# SAO_Area3001_S_WS2812_00.net
KiCad netlist of a schematic drawn in Altium Designer
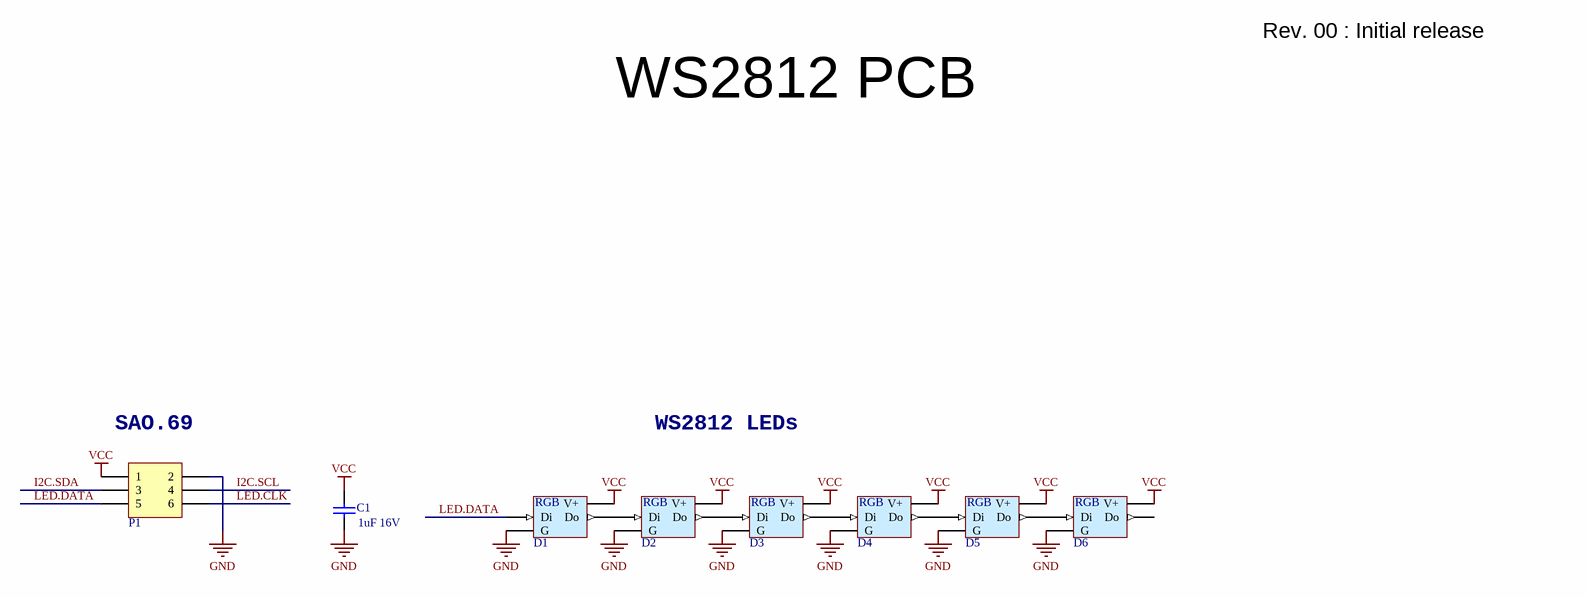
[diagram p0: SAO_Area3001_S_WS2812_00.SchDoc]

(export (version "E")
  (design (tool "Eeschema 10.0.6"))
  (components
    (comp (ref "C1")
      (value "1uF 16V")
      (footprint "C0603_N")
      (description "Capacitor Ceramic")
      (fields (field (name "Comment") "CAP_CERAMIC"))
      (libsource (lib "Phyx_Components") (part "CAP_CERAMIC"))
    )
    (comp (ref "D1")
      (value "WS2812 based digital RGB LED 2022 package")
      (footprint "LED_2022_WS2812B")
      (description "LED # RGB WS2812B-2022")
      (libsource (lib "Phyx_Components") (part "LED_RGB_WS2812B_2022"))
    )
    (comp (ref "D2")
      (value "WS2812 based digital RGB LED 2022 package")
      (footprint "LED_2022_WS2812B")
      (description "LED # RGB WS2812B-2022")
      (libsource (lib "Phyx_Components") (part "LED_RGB_WS2812B_2022"))
    )
    (comp (ref "D3")
      (value "WS2812 based digital RGB LED 2022 package")
      (footprint "LED_2022_WS2812B")
      (description "LED # RGB WS2812B-2022")
      (libsource (lib "Phyx_Components") (part "LED_RGB_WS2812B_2022"))
    )
    (comp (ref "D4")
      (value "WS2812 based digital RGB LED 2022 package")
      (footprint "LED_2022_WS2812B")
      (description "LED # RGB WS2812B-2022")
      (libsource (lib "Phyx_Components") (part "LED_RGB_WS2812B_2022"))
    )
    (comp (ref "D5")
      (value "WS2812 based digital RGB LED 2022 package")
      (footprint "LED_2022_WS2812B")
      (description "LED # RGB WS2812B-2022")
      (libsource (lib "Phyx_Components") (part "LED_RGB_WS2812B_2022"))
    )
    (comp (ref "D6")
      (value "WS2812 based digital RGB LED 2022 package")
      (footprint "LED_2022_WS2812B")
      (description "LED # RGB WS2812B-2022")
      (libsource (lib "Phyx_Components") (part "LED_RGB_WS2812B_2022"))
    )
    (comp (ref "P1")
      (value "Boxed Header 3X2")
      (footprint "HDR2X3_SMD")
      (libsource (lib "Phyx_Components") (part "Header 3X2"))
    )
  )
  (nets
    (net (code "1") (name "/I2C.SCL") (class "Default")
      (node (ref "P1") (pin "4") (pinfunction "4_4") (pintype "passive"))
    )
    (net (code "2") (name "/I2C.SDA") (class "Default")
      (node (ref "P1") (pin "3") (pinfunction "3_3") (pintype "passive"))
    )
    (net (code "3") (name "/LED.CLK") (class "Default")
      (node (ref "P1") (pin "6") (pinfunction "6_6") (pintype "passive"))
    )
    (net (code "4") (name "/LED.DATA") (class "Default")
      (node (ref "D1") (pin "3") (pinfunction "Di_3") (pintype "input"))
      (node (ref "P1") (pin "5") (pinfunction "5_5") (pintype "passive"))
    )
    (net (code "5") (name "GND") (class "Default")
      (node (ref "C1") (pin "2") (pinfunction "2_2") (pintype "passive"))
      (node (ref "D1") (pin "2") (pinfunction "G_2") (pintype "power_in"))
      (node (ref "D2") (pin "2") (pinfunction "G_2") (pintype "power_in"))
      (node (ref "D3") (pin "2") (pinfunction "G_2") (pintype "power_in"))
      (node (ref "D4") (pin "2") (pinfunction "G_2") (pintype "power_in"))
      (node (ref "D5") (pin "2") (pinfunction "G_2") (pintype "power_in"))
      (node (ref "D6") (pin "2") (pinfunction "G_2") (pintype "power_in"))
      (node (ref "P1") (pin "2") (pinfunction "2_2") (pintype "passive"))
    )
    (net (code "6") (name "Net-(D1-Do)") (class "Default")
      (node (ref "D1") (pin "1") (pinfunction "Do_1") (pintype "output"))
      (node (ref "D2") (pin "3") (pinfunction "Di_3") (pintype "input"))
    )
    (net (code "7") (name "Net-(D2-Do)") (class "Default")
      (node (ref "D2") (pin "1") (pinfunction "Do_1") (pintype "output"))
      (node (ref "D3") (pin "3") (pinfunction "Di_3") (pintype "input"))
    )
    (net (code "8") (name "Net-(D3-Do)") (class "Default")
      (node (ref "D3") (pin "1") (pinfunction "Do_1") (pintype "output"))
      (node (ref "D4") (pin "3") (pinfunction "Di_3") (pintype "input"))
    )
    (net (code "9") (name "Net-(D4-Do)") (class "Default")
      (node (ref "D4") (pin "1") (pinfunction "Do_1") (pintype "output"))
      (node (ref "D5") (pin "3") (pinfunction "Di_3") (pintype "input"))
    )
    (net (code "10") (name "Net-(D5-Do)") (class "Default")
      (node (ref "D5") (pin "1") (pinfunction "Do_1") (pintype "output"))
      (node (ref "D6") (pin "3") (pinfunction "Di_3") (pintype "input"))
    )
    (net (code "11") (name "VCC") (class "Default")
      (node (ref "C1") (pin "1") (pinfunction "1_1") (pintype "passive"))
      (node (ref "D1") (pin "4") (pinfunction "V+_4") (pintype "power_in"))
      (node (ref "D2") (pin "4") (pinfunction "V+_4") (pintype "power_in"))
      (node (ref "D3") (pin "4") (pinfunction "V+_4") (pintype "power_in"))
      (node (ref "D4") (pin "4") (pinfunction "V+_4") (pintype "power_in"))
      (node (ref "D5") (pin "4") (pinfunction "V+_4") (pintype "power_in"))
      (node (ref "D6") (pin "4") (pinfunction "V+_4") (pintype "power_in"))
      (node (ref "P1") (pin "1") (pinfunction "1_1") (pintype "passive"))
    )
    (net (code "12") (name "unconnected-(D6-Do-Pad1)") (class "Default")
      (node (ref "D6") (pin "1") (pinfunction "Do_1") (pintype "output"))
    )
  )
)
